# POVDisplayBase.net
KiCad netlist of a schematic drawn in EAGLE
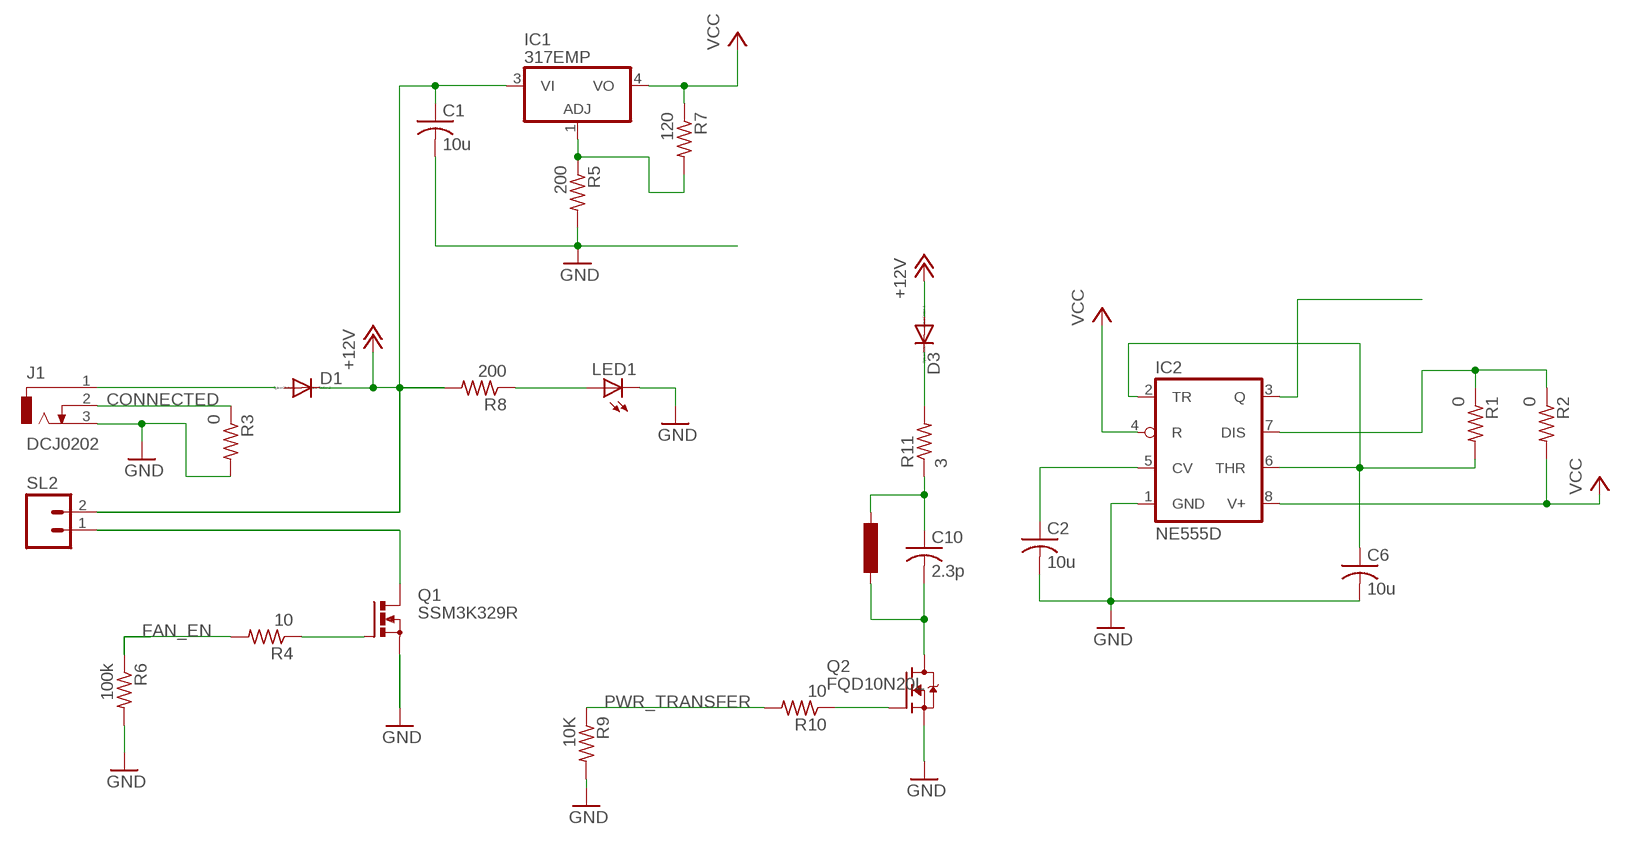
[diagram p0: schematic, sheet 1]

(export (version "E")
  (design (tool "Eeschema 10.0.6"))
  (components
    (comp (ref "C1")
      (value "10u")
      (footprint "eagle-import:C0603")
      (libsource (lib "eagle-import") (part "C-USC0603"))
    )
    (comp (ref "C2")
      (value "10u")
      (footprint "eagle-import:C0603")
      (libsource (lib "eagle-import") (part "C-USC0603"))
    )
    (comp (ref "C6")
      (value "10u")
      (footprint "eagle-import:C0603")
      (libsource (lib "eagle-import") (part "C-USC0603"))
    )
    (comp (ref "C10")
      (value "2.3p")
      (footprint "eagle-import:C1210")
      (libsource (lib "eagle-import") (part "C-USC1210"))
    )
    (comp (ref "D1")
      (value "DIODE-DO-214AC")
      (footprint "eagle-import:DO-214AC")
      (libsource (lib "eagle-import") (part "DIODE-DO-214AC"))
    )
    (comp (ref "D3")
      (value "DIODE-SMC")
      (footprint "eagle-import:SMC")
      (libsource (lib "eagle-import") (part "DIODE-SMC"))
    )
    (comp (ref "IC1")
      (value "317EMP")
      (footprint "eagle-import:SOT223")
      (libsource (lib "eagle-import") (part "317EMP"))
    )
    (comp (ref "IC2")
      (value "NE555D")
      (footprint "eagle-import:SO08")
      (libsource (lib "eagle-import") (part "555DNE"))
    )
    (comp (ref "J1")
      (value "DCJ0202")
      (footprint "eagle-import:DCJ0202")
      (libsource (lib "eagle-import") (part "DCJ0202"))
    )
    (comp (ref "LED1")
      (value "LEDCHIPLED_1206")
      (footprint "eagle-import:CHIPLED_1206")
      (libsource (lib "eagle-import") (part "LEDCHIPLED_1206"))
    )
    (comp (ref "Q1")
      (value "SSM3K329R")
      (footprint "eagle-import:SOT23")
      (libsource (lib "eagle-import") (part "SSM3K329R"))
    )
    (comp (ref "Q2")
      (value "FQD10N20L")
      (footprint "eagle-import:TO252")
      (libsource (lib "eagle-import") (part "FQD10N20L"))
    )
    (comp (ref "R1")
      (value "0")
      (footprint "eagle-import:R0603")
      (libsource (lib "eagle-import") (part "R-US_R0603"))
    )
    (comp (ref "R2")
      (value "0")
      (footprint "eagle-import:R0603")
      (libsource (lib "eagle-import") (part "R-US_R0603"))
    )
    (comp (ref "R3")
      (value "0")
      (footprint "eagle-import:R0603")
      (libsource (lib "eagle-import") (part "R-US_R0603"))
    )
    (comp (ref "R4")
      (value "10")
      (footprint "eagle-import:R0603")
      (libsource (lib "eagle-import") (part "R-US_R0603"))
    )
    (comp (ref "R5")
      (value "200")
      (footprint "eagle-import:R0603")
      (libsource (lib "eagle-import") (part "R-US_R0603"))
    )
    (comp (ref "R6")
      (value "100k")
      (footprint "eagle-import:R0603")
      (libsource (lib "eagle-import") (part "R-US_R0603"))
    )
    (comp (ref "R7")
      (value "120")
      (footprint "eagle-import:R0603")
      (libsource (lib "eagle-import") (part "R-US_R0603"))
    )
    (comp (ref "R8")
      (value "200")
      (footprint "eagle-import:R0603")
      (libsource (lib "eagle-import") (part "R-US_R0603"))
    )
    (comp (ref "R9")
      (value "10K")
      (footprint "eagle-import:R0603")
      (libsource (lib "eagle-import") (part "R-US_R0603"))
    )
    (comp (ref "R10")
      (value "10")
      (footprint "eagle-import:R0603")
      (libsource (lib "eagle-import") (part "R-US_R0603"))
    )
    (comp (ref "R11")
      (value "3")
      (footprint "eagle-import:R1210")
      (libsource (lib "eagle-import") (part "R-US_R1210"))
    )
    (comp (ref "SL2")
      (value "M02")
      (footprint "eagle-import:02P")
      (libsource (lib "eagle-import") (part "M02"))
    )
  )
  (nets
    (net (code "1") (name "+12V") (class "Default")
      (node (ref "C1") (pin "1") (pinfunction "1_1") (pintype "passive"))
      (node (ref "D1") (pin "C") (pinfunction "C_C") (pintype "passive"))
      (node (ref "D3") (pin "A") (pinfunction "A_A") (pintype "passive"))
      (node (ref "IC1") (pin "3") (pinfunction "VI_3") (pintype "input"))
      (node (ref "R8") (pin "2") (pinfunction "2_2") (pintype "passive"))
      (node (ref "SL2") (pin "2") (pinfunction "2_2") (pintype "passive"))
    )
    (net (code "2") (name "/CONNECTED") (class "Default")
      (node (ref "J1") (pin "2") (pinfunction "2_2") (pintype "passive"))
      (node (ref "R3") (pin "1") (pinfunction "1_1") (pintype "passive"))
    )
    (net (code "3") (name "/FAN_EN") (class "Default")
      (node (ref "R4") (pin "2") (pinfunction "2_2") (pintype "passive"))
      (node (ref "R6") (pin "1") (pinfunction "1_1") (pintype "passive"))
    )
    (net (code "4") (name "/PWR_TRANSFER") (class "Default")
      (node (ref "R10") (pin "2") (pinfunction "2_2") (pintype "passive"))
      (node (ref "R9") (pin "1") (pinfunction "1_1") (pintype "passive"))
    )
    (net (code "5") (name "GND") (class "Default")
      (node (ref "C1") (pin "2") (pinfunction "2_2") (pintype "passive"))
      (node (ref "C2") (pin "2") (pinfunction "2_2") (pintype "passive"))
      (node (ref "C6") (pin "2") (pinfunction "2_2") (pintype "passive"))
      (node (ref "IC2") (pin "1") (pinfunction "GND_1") (pintype "power_in"))
      (node (ref "J1") (pin "3") (pinfunction "3_3") (pintype "passive"))
      (node (ref "LED1") (pin "C") (pinfunction "C_C") (pintype "passive"))
      (node (ref "Q1") (pin "2") (pinfunction "S_2") (pintype "passive"))
      (node (ref "Q2") (pin "2") (pinfunction "S_2") (pintype "passive"))
      (node (ref "R3") (pin "2") (pinfunction "2_2") (pintype "passive"))
      (node (ref "R5") (pin "2") (pinfunction "2_2") (pintype "passive"))
      (node (ref "R6") (pin "2") (pinfunction "2_2") (pintype "passive"))
      (node (ref "R9") (pin "2") (pinfunction "2_2") (pintype "passive"))
    )
    (net (code "6") (name "Net-(C10-Pad1)") (class "Default")
      (node (ref "C10") (pin "1") (pinfunction "1_1") (pintype "passive"))
      (node (ref "R11") (pin "1") (pinfunction "1_1") (pintype "passive"))
    )
    (net (code "7") (name "Net-(D3-PadC)") (class "Default")
      (node (ref "D3") (pin "C") (pinfunction "C_C") (pintype "passive"))
      (node (ref "R11") (pin "2") (pinfunction "2_2") (pintype "passive"))
    )
    (net (code "8") (name "Net-(IC1-ADJ)") (class "Default")
      (node (ref "IC1") (pin "1") (pinfunction "ADJ_1") (pintype "input"))
      (node (ref "R5") (pin "1") (pinfunction "1_1") (pintype "passive"))
      (node (ref "R7") (pin "2") (pinfunction "2_2") (pintype "passive"))
    )
    (net (code "9") (name "Net-(IC2-CV)") (class "Default")
      (node (ref "C2") (pin "1") (pinfunction "1_1") (pintype "passive"))
      (node (ref "IC2") (pin "5") (pinfunction "CV_5") (pintype "input"))
    )
    (net (code "10") (name "Net-(IC2-DIS)") (class "Default")
      (node (ref "IC2") (pin "7") (pinfunction "DIS_7") (pintype "input"))
      (node (ref "R1") (pin "1") (pinfunction "1_1") (pintype "passive"))
      (node (ref "R2") (pin "1") (pinfunction "1_1") (pintype "passive"))
    )
    (net (code "11") (name "Net-(IC2-THR)") (class "Default")
      (node (ref "C6") (pin "1") (pinfunction "1_1") (pintype "passive"))
      (node (ref "IC2") (pin "2") (pinfunction "TR_2") (pintype "input"))
      (node (ref "IC2") (pin "6") (pinfunction "THR_6") (pintype "input"))
      (node (ref "R1") (pin "2") (pinfunction "2_2") (pintype "passive"))
    )
    (net (code "12") (name "Net-(LED1-PadA)") (class "Default")
      (node (ref "LED1") (pin "A") (pinfunction "A_A") (pintype "passive"))
      (node (ref "R8") (pin "1") (pinfunction "1_1") (pintype "passive"))
    )
    (net (code "13") (name "Net-(Q1-D)") (class "Default")
      (node (ref "Q1") (pin "3") (pinfunction "D_3") (pintype "passive"))
      (node (ref "SL2") (pin "1") (pinfunction "1_1") (pintype "passive"))
    )
    (net (code "14") (name "Net-(Q1-G)") (class "Default")
      (node (ref "Q1") (pin "1") (pinfunction "G_1") (pintype "passive"))
      (node (ref "R4") (pin "1") (pinfunction "1_1") (pintype "passive"))
    )
    (net (code "15") (name "Net-(Q2-D)") (class "Default")
      (node (ref "C10") (pin "2") (pinfunction "2_2") (pintype "passive"))
      (node (ref "Q2") (pin "3") (pinfunction "D_3") (pintype "passive"))
    )
    (net (code "16") (name "Net-(Q2-G)") (class "Default")
      (node (ref "Q2") (pin "1") (pinfunction "G_1") (pintype "passive"))
      (node (ref "R10") (pin "1") (pinfunction "1_1") (pintype "passive"))
    )
    (net (code "17") (name "VCC") (class "Default")
      (node (ref "IC1") (pin "4") (pinfunction "VO_4") (pintype "passive"))
      (node (ref "IC2") (pin "4") (pinfunction "R_4") (pintype "input"))
      (node (ref "IC2") (pin "8") (pinfunction "V+_8") (pintype "power_in"))
      (node (ref "R2") (pin "2") (pinfunction "2_2") (pintype "passive"))
      (node (ref "R7") (pin "1") (pinfunction "1_1") (pintype "passive"))
    )
    (net (code "18") (name "unconnected-(D1-PadA)") (class "Default")
      (node (ref "D1") (pin "A") (pinfunction "A_A") (pintype "passive"))
    )
    (net (code "19") (name "unconnected-(IC2-Q-Pad3)") (class "Default")
      (node (ref "IC2") (pin "3") (pinfunction "Q_3") (pintype "output"))
    )
    (net (code "20") (name "unconnected-(J1-Pad1)") (class "Default")
      (node (ref "J1") (pin "1") (pinfunction "1_1") (pintype "passive"))
    )
  )
)
